# hiiri627v07.net
KiCad netlist of a schematic drawn in EAGLE
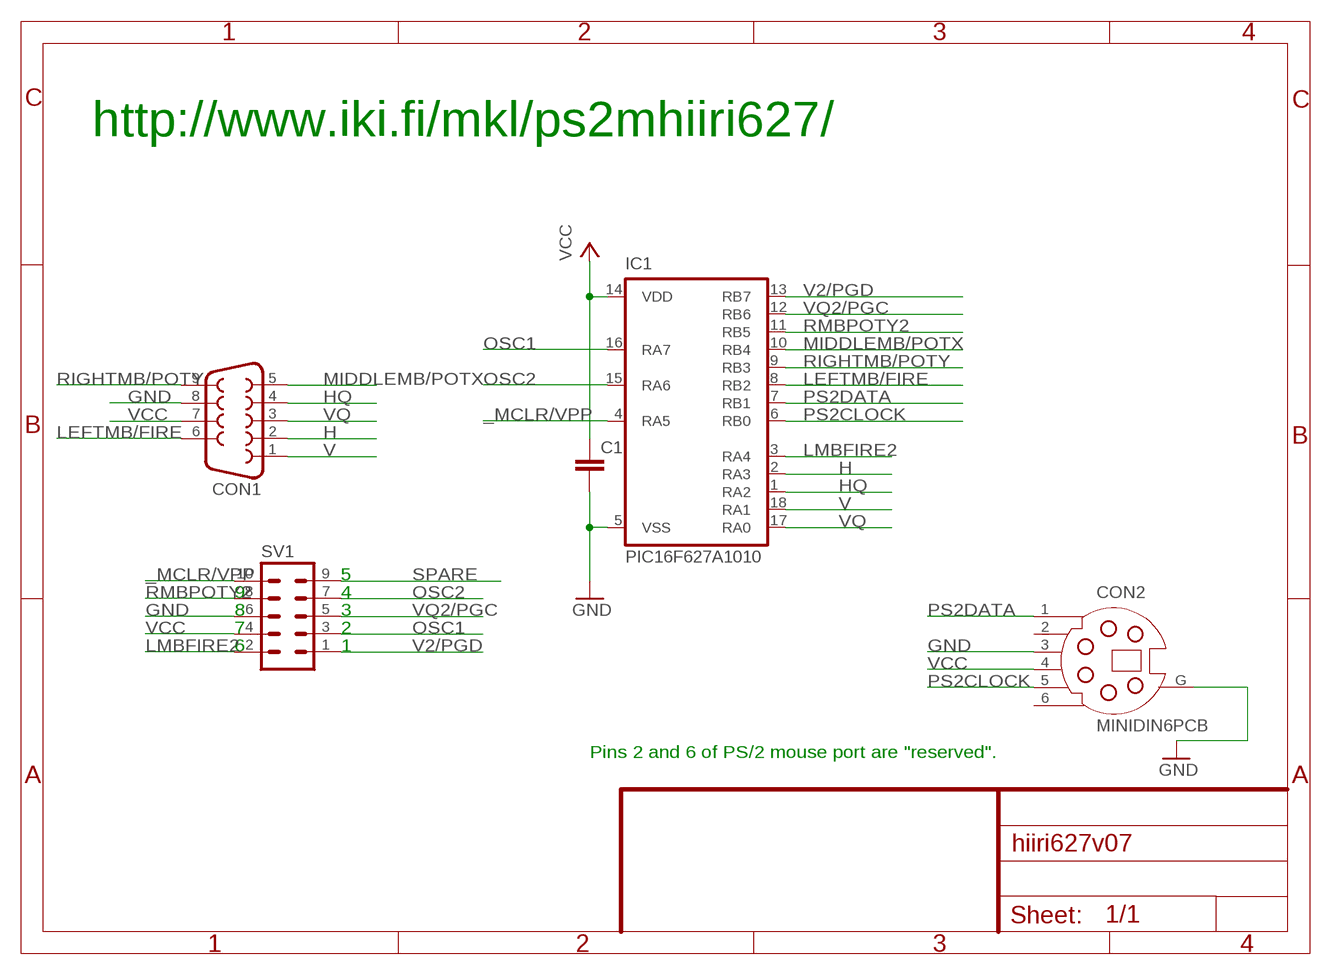
[diagram p0: schematic, sheet 1]

(export (version "E")
  (design (tool "Eeschema 10.0.6"))
  (components
    (comp (ref "C1")
      (value "C-EUC0805K")
      (footprint "eagle-import:C0805K")
      (libsource (lib "eagle-import") (part "C-EUC0805K"))
    )
    (comp (ref "CON1")
      (value "F09D")
      (footprint "eagle-import:F09D")
      (libsource (lib "eagle-import") (part "F09D"))
    )
    (comp (ref "CON2")
      (value "MINIDIN6PCB")
      (footprint "eagle-import:MINIDIN6PCB")
      (libsource (lib "eagle-import") (part "MINIDIN6PCB"))
    )
    (comp (ref "IC1")
      (value "PIC16F627A1010")
      (footprint "eagle-import:SO18-10101020")
      (libsource (lib "eagle-import") (part "PIC16F627A1010"))
    )
    (comp (ref "SV1")
      (value "ML10")
      (footprint "eagle-import:ML10")
      (libsource (lib "eagle-import") (part "ML10"))
    )
  )
  (nets
    (net (code "1") (name "/H") (class "Default")
      (node (ref "CON1") (pin "2") (pinfunction "2_2") (pintype "passive"))
      (node (ref "IC1") (pin "2") (pinfunction "RA3_2") (pintype "bidirectional"))
    )
    (net (code "2") (name "/HQ") (class "Default")
      (node (ref "CON1") (pin "4") (pinfunction "4_4") (pintype "passive"))
      (node (ref "IC1") (pin "1") (pinfunction "RA2_1") (pintype "bidirectional"))
    )
    (net (code "3") (name "/LEFTMB{slash}FIRE") (class "Default")
      (node (ref "CON1") (pin "6") (pinfunction "6_6") (pintype "passive"))
      (node (ref "IC1") (pin "8") (pinfunction "RB2_8") (pintype "bidirectional"))
    )
    (net (code "4") (name "/LMBFIRE2") (class "Default")
      (node (ref "IC1") (pin "3") (pinfunction "RA4_3") (pintype "bidirectional"))
      (node (ref "SV1") (pin "2") (pinfunction "2_2") (pintype "passive"))
    )
    (net (code "5") (name "/MIDDLEMB{slash}POTX") (class "Default")
      (node (ref "CON1") (pin "5") (pinfunction "5_5") (pintype "passive"))
      (node (ref "IC1") (pin "10") (pinfunction "RB4_10") (pintype "bidirectional"))
    )
    (net (code "6") (name "/OSC1") (class "Default")
      (node (ref "IC1") (pin "16") (pinfunction "RA7_16") (pintype "bidirectional"))
      (node (ref "SV1") (pin "3") (pinfunction "3_3") (pintype "passive"))
    )
    (net (code "7") (name "/OSC2") (class "Default")
      (node (ref "IC1") (pin "15") (pinfunction "RA6_15") (pintype "bidirectional"))
      (node (ref "SV1") (pin "7") (pinfunction "7_7") (pintype "passive"))
    )
    (net (code "8") (name "/PS2CLOCK") (class "Default")
      (node (ref "CON2") (pin "5") (pinfunction "5_5") (pintype "passive"))
      (node (ref "IC1") (pin "6") (pinfunction "RB0_6") (pintype "bidirectional"))
    )
    (net (code "9") (name "/PS2DATA") (class "Default")
      (node (ref "CON2") (pin "1") (pinfunction "1_1") (pintype "passive"))
      (node (ref "IC1") (pin "7") (pinfunction "RB1_7") (pintype "bidirectional"))
    )
    (net (code "10") (name "/RIGHTMB{slash}POTY") (class "Default")
      (node (ref "CON1") (pin "9") (pinfunction "9_9") (pintype "passive"))
      (node (ref "IC1") (pin "9") (pinfunction "RB3_9") (pintype "bidirectional"))
    )
    (net (code "11") (name "/RMBPOTY2") (class "Default")
      (node (ref "IC1") (pin "11") (pinfunction "RB5_11") (pintype "bidirectional"))
      (node (ref "SV1") (pin "8") (pinfunction "8_8") (pintype "passive"))
    )
    (net (code "12") (name "/SPARE") (class "Default")
      (node (ref "SV1") (pin "9") (pinfunction "9_9") (pintype "passive"))
    )
    (net (code "13") (name "/V") (class "Default")
      (node (ref "CON1") (pin "1") (pinfunction "1_1") (pintype "passive"))
      (node (ref "IC1") (pin "18") (pinfunction "RA1_18") (pintype "bidirectional"))
    )
    (net (code "14") (name "/V2{slash}PGD") (class "Default")
      (node (ref "IC1") (pin "13") (pinfunction "RB7_13") (pintype "bidirectional"))
      (node (ref "SV1") (pin "1") (pinfunction "1_1") (pintype "passive"))
    )
    (net (code "15") (name "/VQ") (class "Default")
      (node (ref "CON1") (pin "3") (pinfunction "3_3") (pintype "passive"))
      (node (ref "IC1") (pin "17") (pinfunction "RA0_17") (pintype "bidirectional"))
    )
    (net (code "16") (name "/VQ2{slash}PGC") (class "Default")
      (node (ref "IC1") (pin "12") (pinfunction "RB6_12") (pintype "bidirectional"))
      (node (ref "SV1") (pin "5") (pinfunction "5_5") (pintype "passive"))
    )
    (net (code "17") (name "/_MCLR{slash}VPP") (class "Default")
      (node (ref "IC1") (pin "4") (pinfunction "RA5_4") (pintype "input"))
      (node (ref "SV1") (pin "10") (pinfunction "10_10") (pintype "passive"))
    )
    (net (code "18") (name "GND") (class "Default")
      (node (ref "C1") (pin "2") (pinfunction "2_2") (pintype "passive"))
      (node (ref "CON1") (pin "8") (pinfunction "8_8") (pintype "passive"))
      (node (ref "CON2") (pin "3") (pinfunction "3_3") (pintype "passive"))
      (node (ref "CON2") (pin "G") (pinfunction "G_G") (pintype "passive"))
      (node (ref "IC1") (pin "5") (pinfunction "VSS_5") (pintype "power_in"))
      (node (ref "SV1") (pin "6") (pinfunction "6_6") (pintype "passive"))
    )
    (net (code "19") (name "VCC") (class "Default")
      (node (ref "C1") (pin "1") (pinfunction "1_1") (pintype "passive"))
      (node (ref "CON1") (pin "7") (pinfunction "7_7") (pintype "passive"))
      (node (ref "CON2") (pin "4") (pinfunction "4_4") (pintype "passive"))
      (node (ref "IC1") (pin "14") (pinfunction "VDD_14") (pintype "power_in"))
      (node (ref "SV1") (pin "4") (pinfunction "4_4") (pintype "passive"))
    )
    (net (code "20") (name "unconnected-(CON2-Pad2)") (class "Default")
      (node (ref "CON2") (pin "2") (pinfunction "2_2") (pintype "passive"))
    )
    (net (code "21") (name "unconnected-(CON2-Pad6)") (class "Default")
      (node (ref "CON2") (pin "6") (pinfunction "6_6") (pintype "passive"))
    )
  )
)
